# mega128-brd.net
KiCad netlist of a schematic drawn in EAGLE
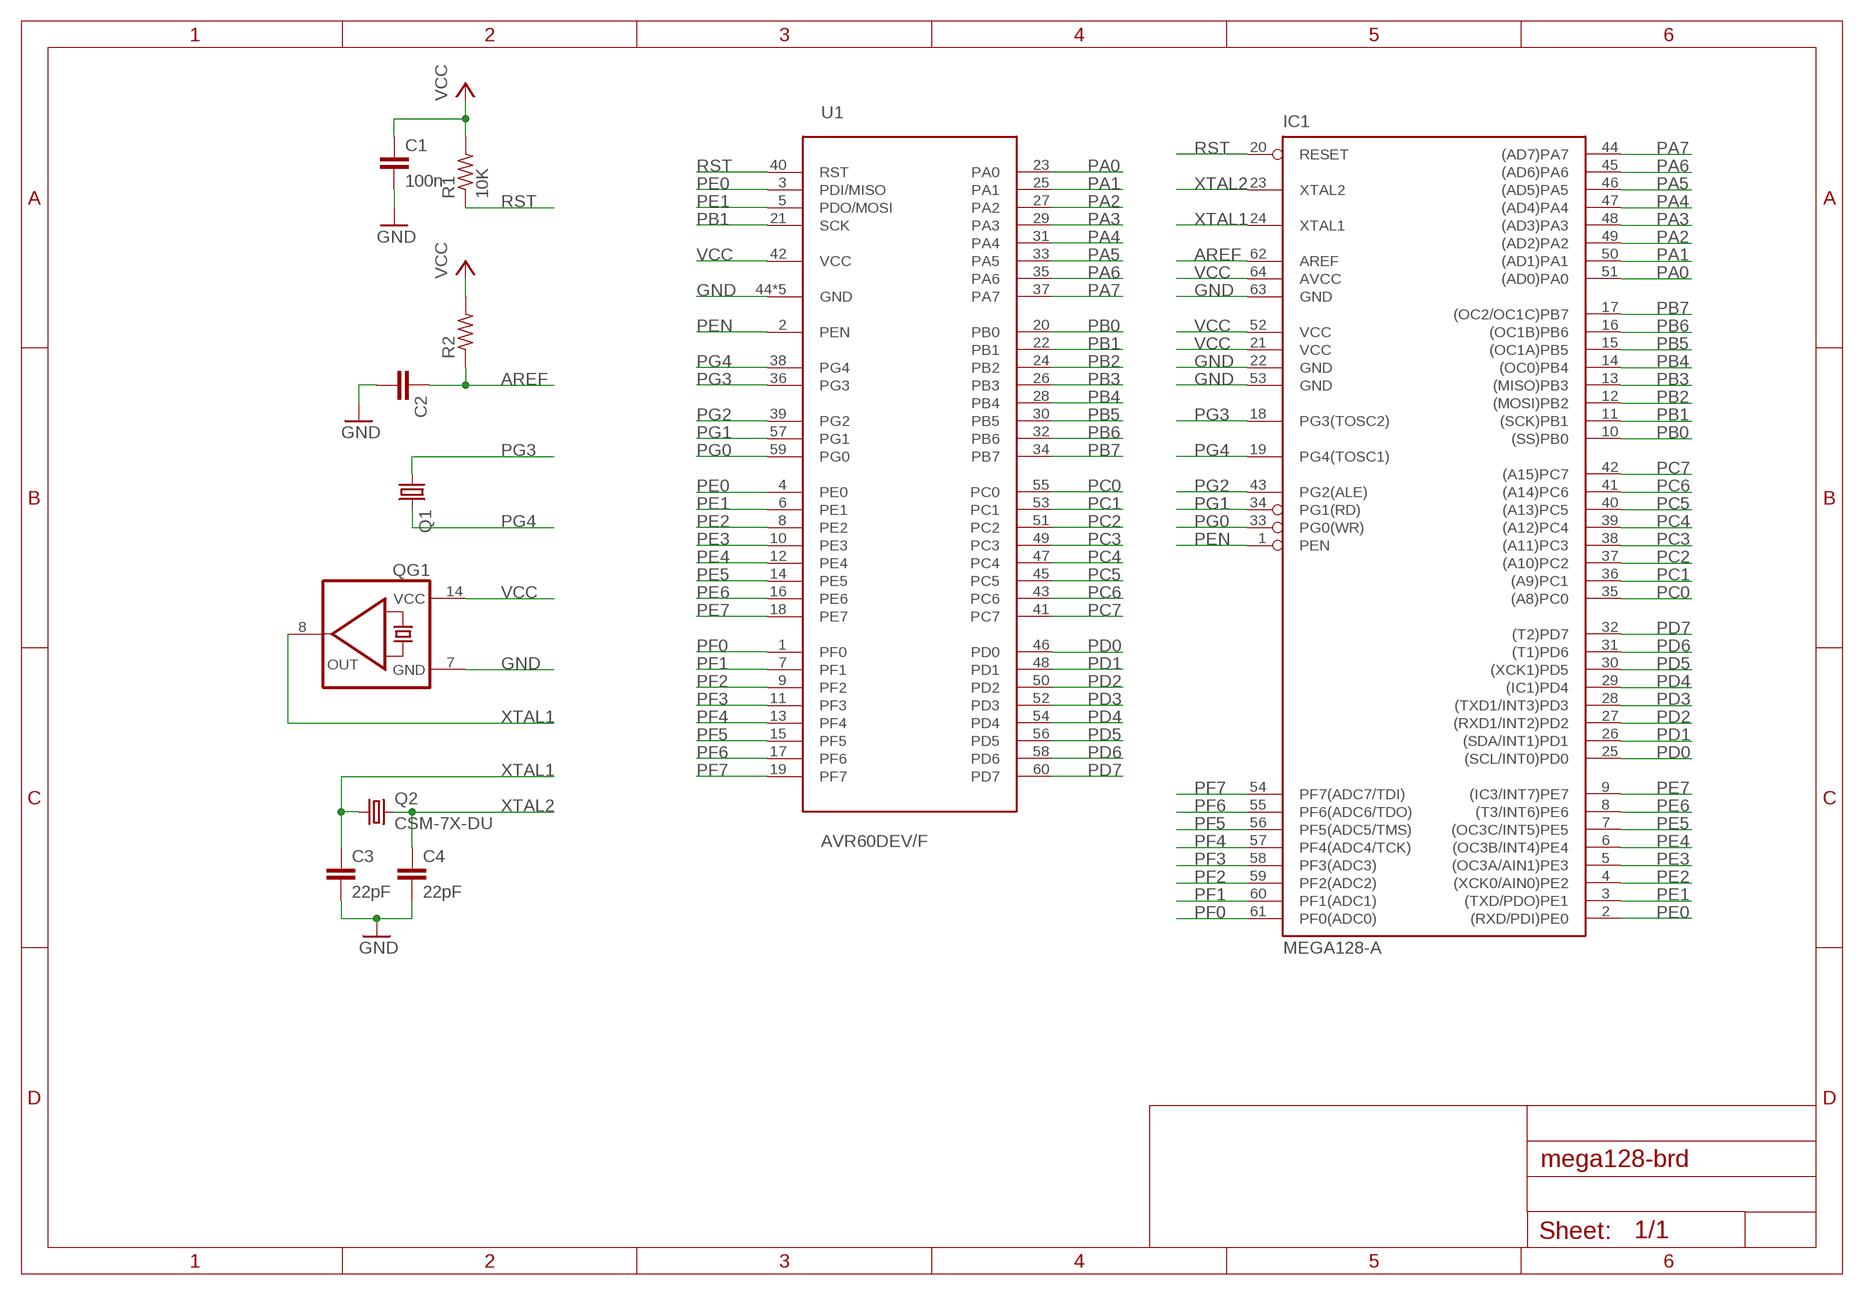
[diagram p0: schematic, sheet 1]

(export (version "E")
  (design (tool "Eeschema 10.0.6"))
  (components
    (comp (ref "C1")
      (value "100n")
      (footprint "eagle-import:C0805")
      (libsource (lib "eagle-import") (part "C-EUC0805"))
    )
    (comp (ref "C2")
      (value "C-EUC0805")
      (footprint "eagle-import:C0805")
      (libsource (lib "eagle-import") (part "C-EUC0805"))
    )
    (comp (ref "C3")
      (value "22pF")
      (footprint "eagle-import:C0805")
      (libsource (lib "eagle-import") (part "C-EUC0805"))
    )
    (comp (ref "C4")
      (value "22pF")
      (footprint "eagle-import:C0805")
      (libsource (lib "eagle-import") (part "C-EUC0805"))
    )
    (comp (ref "IC1")
      (value "MEGA128-A")
      (footprint "eagle-import:TQFP64")
      (fields (field (name "MPN") "ATMEGA128-16AU"))
      (libsource (lib "eagle-import") (part "MEGA128-A"))
    )
    (comp (ref "Q1")
      (value "CRYSTALTC26V")
      (footprint "eagle-import:TC26V")
      (libsource (lib "eagle-import") (part "CRYSTALTC26V"))
    )
    (comp (ref "Q2")
      (value "CSM-7X-DU")
      (footprint "eagle-import:CSM-7X-DU")
      (libsource (lib "eagle-import") (part "CSM-7X-DU"))
    )
    (comp (ref "QG1")
      (value "QG5860")
      (footprint "eagle-import:DIL14S")
      (libsource (lib "eagle-import") (part "QG5860"))
    )
    (comp (ref "R1")
      (value "10K")
      (footprint "eagle-import:R0805")
      (libsource (lib "eagle-import") (part "R-US_R0805"))
    )
    (comp (ref "R2")
      (value "R-US_R0805")
      (footprint "eagle-import:R0805")
      (libsource (lib "eagle-import") (part "R-US_R0805"))
    )
    (comp (ref "U1")
      (value "AVR60DEV/F")
      (footprint "eagle-import:AVR60-DEV")
      (libsource (lib "eagle-import") (part "AVR60DEV/F"))
    )
  )
  (nets
    (net (code "1") (name "/AREF") (class "Default")
      (node (ref "C2") (pin "1") (pinfunction "1_1") (pintype "passive"))
      (node (ref "IC1") (pin "62") (pinfunction "AREF_62") (pintype "passive"))
      (node (ref "R2") (pin "1") (pinfunction "1_1") (pintype "passive"))
    )
    (net (code "2") (name "/PA0") (class "Default")
      (node (ref "IC1") (pin "51") (pinfunction "(AD0)PA0_51") (pintype "bidirectional"))
      (node (ref "U1") (pin "23") (pinfunction "PA0_23") (pintype "bidirectional"))
    )
    (net (code "3") (name "/PA1") (class "Default")
      (node (ref "IC1") (pin "50") (pinfunction "(AD1)PA1_50") (pintype "bidirectional"))
      (node (ref "U1") (pin "25") (pinfunction "PA1_25") (pintype "bidirectional"))
    )
    (net (code "4") (name "/PA2") (class "Default")
      (node (ref "IC1") (pin "49") (pinfunction "(AD2)PA2_49") (pintype "bidirectional"))
      (node (ref "U1") (pin "27") (pinfunction "PA2_27") (pintype "bidirectional"))
    )
    (net (code "5") (name "/PA3") (class "Default")
      (node (ref "IC1") (pin "48") (pinfunction "(AD3)PA3_48") (pintype "bidirectional"))
      (node (ref "U1") (pin "29") (pinfunction "PA3_29") (pintype "bidirectional"))
    )
    (net (code "6") (name "/PA4") (class "Default")
      (node (ref "IC1") (pin "47") (pinfunction "(AD4)PA4_47") (pintype "bidirectional"))
      (node (ref "U1") (pin "31") (pinfunction "PA4_31") (pintype "bidirectional"))
    )
    (net (code "7") (name "/PA5") (class "Default")
      (node (ref "IC1") (pin "46") (pinfunction "(AD5)PA5_46") (pintype "bidirectional"))
      (node (ref "U1") (pin "33") (pinfunction "PA5_33") (pintype "bidirectional"))
    )
    (net (code "8") (name "/PA6") (class "Default")
      (node (ref "IC1") (pin "45") (pinfunction "(AD6)PA6_45") (pintype "bidirectional"))
      (node (ref "U1") (pin "35") (pinfunction "PA6_35") (pintype "bidirectional"))
    )
    (net (code "9") (name "/PA7") (class "Default")
      (node (ref "IC1") (pin "44") (pinfunction "(AD7)PA7_44") (pintype "bidirectional"))
      (node (ref "U1") (pin "37") (pinfunction "PA7_37") (pintype "bidirectional"))
    )
    (net (code "10") (name "/PB0") (class "Default")
      (node (ref "IC1") (pin "10") (pinfunction "(SS)PB0_10") (pintype "bidirectional"))
      (node (ref "U1") (pin "20") (pinfunction "PB0_20") (pintype "bidirectional"))
    )
    (net (code "11") (name "/PB1") (class "Default")
      (node (ref "IC1") (pin "11") (pinfunction "(SCK)PB1_11") (pintype "bidirectional"))
      (node (ref "U1") (pin "21") (pinfunction "SCK_21") (pintype "bidirectional"))
      (node (ref "U1") (pin "22") (pinfunction "PB1_22") (pintype "bidirectional"))
    )
    (net (code "12") (name "/PB2") (class "Default")
      (node (ref "IC1") (pin "12") (pinfunction "(MOSI)PB2_12") (pintype "bidirectional"))
      (node (ref "U1") (pin "24") (pinfunction "PB2_24") (pintype "bidirectional"))
    )
    (net (code "13") (name "/PB3") (class "Default")
      (node (ref "IC1") (pin "13") (pinfunction "(MISO)PB3_13") (pintype "bidirectional"))
      (node (ref "U1") (pin "26") (pinfunction "PB3_26") (pintype "bidirectional"))
    )
    (net (code "14") (name "/PB4") (class "Default")
      (node (ref "IC1") (pin "14") (pinfunction "(OC0)PB4_14") (pintype "bidirectional"))
      (node (ref "U1") (pin "28") (pinfunction "PB4_28") (pintype "bidirectional"))
    )
    (net (code "15") (name "/PB5") (class "Default")
      (node (ref "IC1") (pin "15") (pinfunction "(OC1A)PB5_15") (pintype "bidirectional"))
      (node (ref "U1") (pin "30") (pinfunction "PB5_30") (pintype "bidirectional"))
    )
    (net (code "16") (name "/PB6") (class "Default")
      (node (ref "IC1") (pin "16") (pinfunction "(OC1B)PB6_16") (pintype "bidirectional"))
      (node (ref "U1") (pin "32") (pinfunction "PB6_32") (pintype "bidirectional"))
    )
    (net (code "17") (name "/PB7") (class "Default")
      (node (ref "IC1") (pin "17") (pinfunction "(OC2/OC1C)PB7_17") (pintype "bidirectional"))
      (node (ref "U1") (pin "34") (pinfunction "PB7_34") (pintype "bidirectional"))
    )
    (net (code "18") (name "/PC0") (class "Default")
      (node (ref "IC1") (pin "35") (pinfunction "(A8)PC0_35") (pintype "output"))
      (node (ref "U1") (pin "55") (pinfunction "PC0_55") (pintype "bidirectional"))
    )
    (net (code "19") (name "/PC1") (class "Default")
      (node (ref "IC1") (pin "36") (pinfunction "(A9)PC1_36") (pintype "output"))
      (node (ref "U1") (pin "53") (pinfunction "PC1_53") (pintype "bidirectional"))
    )
    (net (code "20") (name "/PC2") (class "Default")
      (node (ref "IC1") (pin "37") (pinfunction "(A10)PC2_37") (pintype "output"))
      (node (ref "U1") (pin "51") (pinfunction "PC2_51") (pintype "bidirectional"))
    )
    (net (code "21") (name "/PC3") (class "Default")
      (node (ref "IC1") (pin "38") (pinfunction "(A11)PC3_38") (pintype "output"))
      (node (ref "U1") (pin "49") (pinfunction "PC3_49") (pintype "bidirectional"))
    )
    (net (code "22") (name "/PC4") (class "Default")
      (node (ref "IC1") (pin "39") (pinfunction "(A12)PC4_39") (pintype "output"))
      (node (ref "U1") (pin "47") (pinfunction "PC4_47") (pintype "bidirectional"))
    )
    (net (code "23") (name "/PC5") (class "Default")
      (node (ref "IC1") (pin "40") (pinfunction "(A13)PC5_40") (pintype "output"))
      (node (ref "U1") (pin "45") (pinfunction "PC5_45") (pintype "bidirectional"))
    )
    (net (code "24") (name "/PC6") (class "Default")
      (node (ref "IC1") (pin "41") (pinfunction "(A14)PC6_41") (pintype "output"))
      (node (ref "U1") (pin "43") (pinfunction "PC6_43") (pintype "bidirectional"))
    )
    (net (code "25") (name "/PC7") (class "Default")
      (node (ref "IC1") (pin "42") (pinfunction "(A15)PC7_42") (pintype "output"))
      (node (ref "U1") (pin "41") (pinfunction "PC7_41") (pintype "bidirectional"))
    )
    (net (code "26") (name "/PD0") (class "Default")
      (node (ref "IC1") (pin "25") (pinfunction "(SCL/INT0)PD0_25") (pintype "bidirectional"))
      (node (ref "U1") (pin "46") (pinfunction "PD0_46") (pintype "bidirectional"))
    )
    (net (code "27") (name "/PD1") (class "Default")
      (node (ref "IC1") (pin "26") (pinfunction "(SDA/INT1)PD1_26") (pintype "bidirectional"))
      (node (ref "U1") (pin "48") (pinfunction "PD1_48") (pintype "bidirectional"))
    )
    (net (code "28") (name "/PD2") (class "Default")
      (node (ref "IC1") (pin "27") (pinfunction "(RXD1/INT2)PD2_27") (pintype "bidirectional"))
      (node (ref "U1") (pin "50") (pinfunction "PD2_50") (pintype "bidirectional"))
    )
    (net (code "29") (name "/PD3") (class "Default")
      (node (ref "IC1") (pin "28") (pinfunction "(TXD1/INT3)PD3_28") (pintype "bidirectional"))
      (node (ref "U1") (pin "52") (pinfunction "PD3_52") (pintype "bidirectional"))
    )
    (net (code "30") (name "/PD4") (class "Default")
      (node (ref "IC1") (pin "29") (pinfunction "(IC1)PD4_29") (pintype "bidirectional"))
      (node (ref "U1") (pin "54") (pinfunction "PD4_54") (pintype "bidirectional"))
    )
    (net (code "31") (name "/PD5") (class "Default")
      (node (ref "IC1") (pin "30") (pinfunction "(XCK1)PD5_30") (pintype "bidirectional"))
      (node (ref "U1") (pin "56") (pinfunction "PD5_56") (pintype "bidirectional"))
    )
    (net (code "32") (name "/PD6") (class "Default")
      (node (ref "IC1") (pin "31") (pinfunction "(T1)PD6_31") (pintype "bidirectional"))
      (node (ref "U1") (pin "58") (pinfunction "PD6_58") (pintype "bidirectional"))
    )
    (net (code "33") (name "/PD7") (class "Default")
      (node (ref "IC1") (pin "32") (pinfunction "(T2)PD7_32") (pintype "bidirectional"))
      (node (ref "U1") (pin "60") (pinfunction "PD7_60") (pintype "bidirectional"))
    )
    (net (code "34") (name "/PE0") (class "Default")
      (node (ref "IC1") (pin "2") (pinfunction "(RXD/PDI)PE0_2") (pintype "bidirectional"))
      (node (ref "U1") (pin "3") (pinfunction "PDI/MISO_3") (pintype "bidirectional"))
      (node (ref "U1") (pin "4") (pinfunction "PE0_4") (pintype "bidirectional"))
    )
    (net (code "35") (name "/PE1") (class "Default")
      (node (ref "IC1") (pin "3") (pinfunction "(TXD/PDO)PE1_3") (pintype "bidirectional"))
      (node (ref "U1") (pin "5") (pinfunction "PDO/MOSI_5") (pintype "bidirectional"))
      (node (ref "U1") (pin "6") (pinfunction "PE1_6") (pintype "bidirectional"))
    )
    (net (code "36") (name "/PE2") (class "Default")
      (node (ref "IC1") (pin "4") (pinfunction "(XCK0/AIN0)PE2_4") (pintype "bidirectional"))
      (node (ref "U1") (pin "8") (pinfunction "PE2_8") (pintype "bidirectional"))
    )
    (net (code "37") (name "/PE3") (class "Default")
      (node (ref "IC1") (pin "5") (pinfunction "(OC3A/AIN1)PE3_5") (pintype "bidirectional"))
      (node (ref "U1") (pin "10") (pinfunction "PE3_10") (pintype "bidirectional"))
    )
    (net (code "38") (name "/PE4") (class "Default")
      (node (ref "IC1") (pin "6") (pinfunction "(OC3B/INT4)PE4_6") (pintype "bidirectional"))
      (node (ref "U1") (pin "12") (pinfunction "PE4_12") (pintype "bidirectional"))
    )
    (net (code "39") (name "/PE5") (class "Default")
      (node (ref "IC1") (pin "7") (pinfunction "(OC3C/INT5)PE5_7") (pintype "bidirectional"))
      (node (ref "U1") (pin "14") (pinfunction "PE5_14") (pintype "bidirectional"))
    )
    (net (code "40") (name "/PE6") (class "Default")
      (node (ref "IC1") (pin "8") (pinfunction "(T3/INT6)PE6_8") (pintype "bidirectional"))
      (node (ref "U1") (pin "16") (pinfunction "PE6_16") (pintype "bidirectional"))
    )
    (net (code "41") (name "/PE7") (class "Default")
      (node (ref "IC1") (pin "9") (pinfunction "(IC3/INT7)PE7_9") (pintype "bidirectional"))
      (node (ref "U1") (pin "18") (pinfunction "PE7_18") (pintype "bidirectional"))
    )
    (net (code "42") (name "/PEN") (class "Default")
      (node (ref "IC1") (pin "1") (pinfunction "PEN_1") (pintype "input"))
      (node (ref "U1") (pin "2") (pinfunction "PEN_2") (pintype "bidirectional"))
    )
    (net (code "43") (name "/PF0") (class "Default")
      (node (ref "IC1") (pin "61") (pinfunction "PF0(ADC0)_61") (pintype "input"))
      (node (ref "U1") (pin "1") (pinfunction "PF0_1") (pintype "bidirectional"))
    )
    (net (code "44") (name "/PF1") (class "Default")
      (node (ref "IC1") (pin "60") (pinfunction "PF1(ADC1)_60") (pintype "input"))
      (node (ref "U1") (pin "7") (pinfunction "PF1_7") (pintype "bidirectional"))
    )
    (net (code "45") (name "/PF2") (class "Default")
      (node (ref "IC1") (pin "59") (pinfunction "PF2(ADC2)_59") (pintype "input"))
      (node (ref "U1") (pin "9") (pinfunction "PF2_9") (pintype "bidirectional"))
    )
    (net (code "46") (name "/PF3") (class "Default")
      (node (ref "IC1") (pin "58") (pinfunction "PF3(ADC3)_58") (pintype "input"))
      (node (ref "U1") (pin "11") (pinfunction "PF3_11") (pintype "bidirectional"))
    )
    (net (code "47") (name "/PF4") (class "Default")
      (node (ref "IC1") (pin "57") (pinfunction "PF4(ADC4/TCK)_57") (pintype "input"))
      (node (ref "U1") (pin "13") (pinfunction "PF4_13") (pintype "bidirectional"))
    )
    (net (code "48") (name "/PF5") (class "Default")
      (node (ref "IC1") (pin "56") (pinfunction "PF5(ADC5/TMS)_56") (pintype "input"))
      (node (ref "U1") (pin "15") (pinfunction "PF5_15") (pintype "bidirectional"))
    )
    (net (code "49") (name "/PF6") (class "Default")
      (node (ref "IC1") (pin "55") (pinfunction "PF6(ADC6/TDO)_55") (pintype "input"))
      (node (ref "U1") (pin "17") (pinfunction "PF6_17") (pintype "bidirectional"))
    )
    (net (code "50") (name "/PF7") (class "Default")
      (node (ref "IC1") (pin "54") (pinfunction "PF7(ADC7/TDI)_54") (pintype "input"))
      (node (ref "U1") (pin "19") (pinfunction "PF7_19") (pintype "bidirectional"))
    )
    (net (code "51") (name "/PG0") (class "Default")
      (node (ref "IC1") (pin "33") (pinfunction "PG0(WR)_33") (pintype "bidirectional"))
      (node (ref "U1") (pin "59") (pinfunction "PG0_59") (pintype "bidirectional"))
    )
    (net (code "52") (name "/PG1") (class "Default")
      (node (ref "IC1") (pin "34") (pinfunction "PG1(RD)_34") (pintype "bidirectional"))
      (node (ref "U1") (pin "57") (pinfunction "PG1_57") (pintype "bidirectional"))
    )
    (net (code "53") (name "/PG2") (class "Default")
      (node (ref "IC1") (pin "43") (pinfunction "PG2(ALE)_43") (pintype "bidirectional"))
      (node (ref "U1") (pin "39") (pinfunction "PG2_39") (pintype "bidirectional"))
    )
    (net (code "54") (name "/PG3") (class "Default")
      (node (ref "IC1") (pin "18") (pinfunction "PG3(TOSC2)_18") (pintype "bidirectional"))
      (node (ref "Q1") (pin "1") (pinfunction "1_1") (pintype "passive"))
      (node (ref "U1") (pin "36") (pinfunction "PG3_36") (pintype "bidirectional"))
    )
    (net (code "55") (name "/PG4") (class "Default")
      (node (ref "IC1") (pin "19") (pinfunction "PG4(TOSC1)_19") (pintype "bidirectional"))
      (node (ref "Q1") (pin "2") (pinfunction "2_2") (pintype "passive"))
      (node (ref "U1") (pin "38") (pinfunction "PG4_38") (pintype "bidirectional"))
    )
    (net (code "56") (name "/RST") (class "Default")
      (node (ref "IC1") (pin "20") (pinfunction "RESET_20") (pintype "input"))
      (node (ref "R1") (pin "1") (pinfunction "1_1") (pintype "passive"))
      (node (ref "U1") (pin "40") (pinfunction "RST_40") (pintype "bidirectional"))
    )
    (net (code "57") (name "/XTAL1") (class "Default")
      (node (ref "C3") (pin "1") (pinfunction "1_1") (pintype "passive"))
      (node (ref "IC1") (pin "24") (pinfunction "XTAL1_24") (pintype "bidirectional"))
      (node (ref "Q2") (pin "1") (pinfunction "1_1") (pintype "passive"))
      (node (ref "QG1") (pin "8") (pinfunction "OUT_8") (pintype "output"))
    )
    (net (code "58") (name "/XTAL2") (class "Default")
      (node (ref "C4") (pin "1") (pinfunction "1_1") (pintype "passive"))
      (node (ref "IC1") (pin "23") (pinfunction "XTAL2_23") (pintype "bidirectional"))
      (node (ref "Q2") (pin "2") (pinfunction "2_2") (pintype "passive"))
    )
    (net (code "59") (name "GND") (class "Default")
      (node (ref "C1") (pin "2") (pinfunction "2_2") (pintype "passive"))
      (node (ref "C2") (pin "2") (pinfunction "2_2") (pintype "passive"))
      (node (ref "C3") (pin "2") (pinfunction "2_2") (pintype "passive"))
      (node (ref "C4") (pin "2") (pinfunction "2_2") (pintype "passive"))
      (node (ref "IC1") (pin "22") (pinfunction "GND_22") (pintype "power_in"))
      (node (ref "IC1") (pin "53") (pinfunction "GND_53") (pintype "power_in"))
      (node (ref "IC1") (pin "63") (pinfunction "GND_63") (pintype "power_in"))
      (node (ref "QG1") (pin "7") (pinfunction "GND_7") (pintype "power_in"))
      (node (ref "U1") (pin "44") (pinfunction "GND_44") (pintype "bidirectional"))
      (node (ref "U1") (pin "61") (pinfunction "GND_61") (pintype "bidirectional"))
      (node (ref "U1") (pin "62") (pinfunction "GND_62") (pintype "bidirectional"))
      (node (ref "U1") (pin "63") (pinfunction "GND_63") (pintype "bidirectional"))
      (node (ref "U1") (pin "64") (pinfunction "GND_64") (pintype "bidirectional"))
    )
    (net (code "60") (name "VCC") (class "Default")
      (node (ref "C1") (pin "1") (pinfunction "1_1") (pintype "passive"))
      (node (ref "IC1") (pin "21") (pinfunction "VCC_21") (pintype "power_in"))
      (node (ref "IC1") (pin "52") (pinfunction "VCC_52") (pintype "power_in"))
      (node (ref "IC1") (pin "64") (pinfunction "AVCC_64") (pintype "power_in"))
      (node (ref "QG1") (pin "14") (pinfunction "VCC_14") (pintype "power_in"))
      (node (ref "R1") (pin "2") (pinfunction "2_2") (pintype "passive"))
      (node (ref "R2") (pin "2") (pinfunction "2_2") (pintype "passive"))
      (node (ref "U1") (pin "42") (pinfunction "VCC_42") (pintype "bidirectional"))
    )
  )
)
